# wifi.net
KiCad netlist of a schematic drawn in Altium Designer
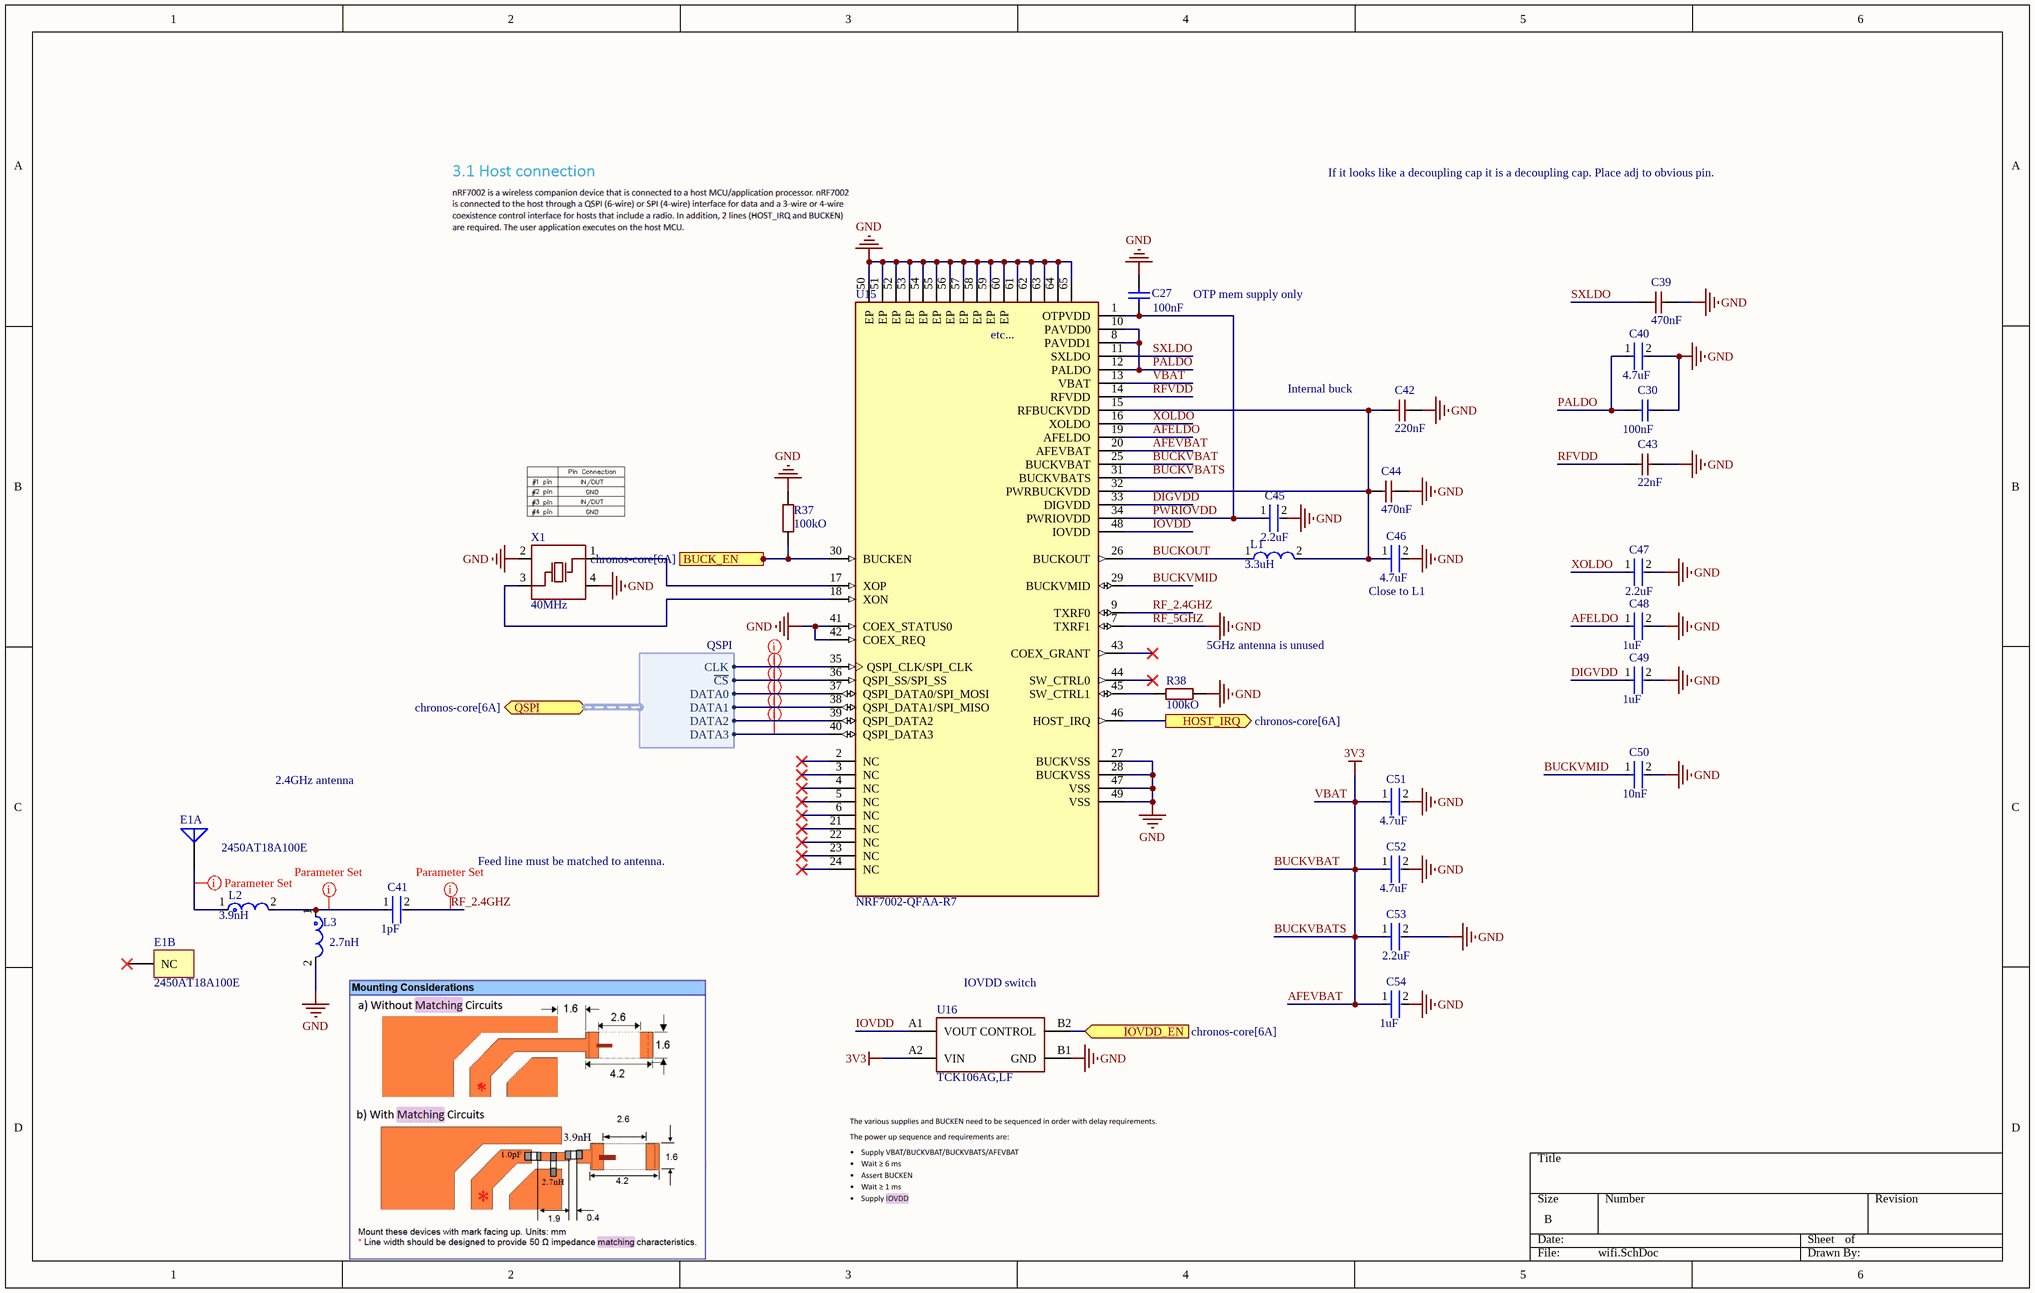
[diagram p0: wifi.SchDoc]

(export (version "E")
  (design (tool "Eeschema 10.0.6"))
  (components
    (comp (ref "C27")
      (value "CL05B104KO5NNNC")
      (footprint "CAPC1050X55X23ML05T13")
      (description "Chip Capacitor, 100 nF, +/- 10%, 16 V, -55 to 125 degC, 0402 (1005 Metric), RoHS, Tape and Reel")
      (fields (field (name "MANUFACTURER") "Samsung Electro-Mechanics") (field (name "CAPACITANCE") "100nF"))
      (libsource (lib "Altium Content Vault") (part "CAP-NP-2"))
    )
    (comp (ref "C30")
      (value "CL05B104KO5NNNC")
      (footprint "CAPC1050X55X23ML05T13")
      (description "Chip Capacitor, 100 nF, +/- 10%, 16 V, -55 to 125 degC, 0402 (1005 Metric), RoHS, Tape and Reel")
      (fields (field (name "MANUFACTURER") "Samsung Electro-Mechanics") (field (name "CAPACITANCE") "100nF"))
      (libsource (lib "Altium Content Vault") (part "CAP-NP-2"))
    )
    (comp (ref "C39")
      (value "470nF")
      (footprint "CL10B474KA8NNNC")
      (fields
        (field (name "JLCPCB PART #") "C1623")
        (field (name "MANUFACTURER PART NUMBER") "CL10B474KA8NNNC")
        (field (name "MANUFACTURER") "Samsung Electro-Mechanics")
      )
      (libsource (lib "CL10B474KA8NNNC") (part "CL10B474KA8NNNC"))
    )
    (comp (ref "C40")
      (value "CL05A475MP5NRNC")
      (footprint "FP-CL282-IPC_C")
      (description "Cap Ceramic 4.7uF 10V X5R ±20% SMD 0402 +85°C Paper T/R")
      (fields (field (name "CAPACITANCE") "4.7uF") (field (name "TOLERANCE") "20%"))
      (libsource (lib "Altium Content Vault") (part "b4654b650e69147ec39a6b967a45e02"))
    )
    (comp (ref "C41")
      (value "GJM1555C1H1R0BB01D")
      (footprint "FP-GJM155-0_05-IPC_B")
      (description "Multi-Layer Ceramic Capacitor 1pF C0G  ±0.1pF 0402 Paper T/R")
      (fields (field (name "CAPACITANCE") "1pF") (field (name "VOLTAGE") "50V"))
      (libsource (lib "Altium Content Vault") (part "02cd4be3c70576c341d710602a673aa"))
    )
    (comp (ref "C42")
      (value "220nF")
      (footprint "CL05B224KO5NNNC")
      (fields
        (field (name "JLCPCB PART #") "C16772")
        (field (name "MANUFACTURER PART NUMBER") "CL05B224KO5NNNC")
        (field (name "MANUFACTURER") "Samsung Electro-Mechanics")
      )
      (libsource (lib "CL05B224KO5NNNC") (part "CL05B224KO5NNNC"))
    )
    (comp (ref "C43")
      (value "22nF")
      (footprint "0402B223K500NT")
      (fields
        (field (name "JLCPCB PART #") "C1532")
        (field (name "MANUFACTURER PART NUMBER") "0402B223K500NT")
        (field (name "MANUFACTURER") "FH (Guangdong Fenghua Advanced Tech)")
      )
      (libsource (lib "0402B223K500NT") (part "0402B223K500NT"))
    )
    (comp (ref "C44")
      (value "470nF")
      (footprint "CL10B474KA8NNNC")
      (fields
        (field (name "JLCPCB PART #") "C1623")
        (field (name "MANUFACTURER PART NUMBER") "CL10B474KA8NNNC")
        (field (name "MANUFACTURER") "Samsung Electro-Mechanics")
      )
      (libsource (lib "CL10B474KA8NNNC") (part "CL10B474KA8NNNC"))
    )
    (comp (ref "C45")
      (value "CL05A225MQ5NSNC")
      (footprint "FP-CL50-IPC_C")
      (description "Cap Ceramic 2.2uF 6.3V X5R ±20% SMD 0402 +85°C Paper T/R")
      (fields (field (name "CAPACITANCE") "2.2uF") (field (name "TOLERANCE") "20%"))
      (libsource (lib "Altium Content Vault") (part "b4654b650e69147ec39a6b967a45e02"))
    )
    (comp (ref "C46")
      (value "CL05A475MP5NRNC")
      (footprint "FP-CL282-IPC_C")
      (description "Cap Ceramic 4.7uF 10V X5R ±20% SMD 0402 +85°C Paper T/R")
      (fields (field (name "CAPACITANCE") "4.7uF") (field (name "TOLERANCE") "20%"))
      (libsource (lib "Altium Content Vault") (part "b4654b650e69147ec39a6b967a45e02"))
    )
    (comp (ref "C47")
      (value "CL05A225MQ5NSNC")
      (footprint "FP-CL50-IPC_C")
      (description "Cap Ceramic 2.2uF 6.3V X5R ±20% SMD 0402 +85°C Paper T/R")
      (fields (field (name "CAPACITANCE") "2.2uF") (field (name "TOLERANCE") "20%"))
      (libsource (lib "Altium Content Vault") (part "b4654b650e69147ec39a6b967a45e02"))
    )
    (comp (ref "C48")
      (value "CL05A105KA5NQNC")
      (footprint "FP-CL542-IPC_C")
      (description "Cap Ceramic 1uF 25V X5R ±10% SMD 0402 +85°C Paper T/R")
      (fields (field (name "CAPACITANCE") "1uF") (field (name "TOLERANCE") "10%"))
      (libsource (lib "Altium Content Vault") (part "b4654b650e69147ec39a6b967a45e02"))
    )
    (comp (ref "C49")
      (value "CL05A105KA5NQNC")
      (footprint "FP-CL542-IPC_C")
      (description "Cap Ceramic 1uF 25V X5R ±10% SMD 0402 +85°C Paper T/R")
      (fields (field (name "CAPACITANCE") "1uF") (field (name "TOLERANCE") "10%"))
      (libsource (lib "Altium Content Vault") (part "b4654b650e69147ec39a6b967a45e02"))
    )
    (comp (ref "C50")
      (value "CL05B103KB5NNNC")
      (footprint "FP-CL165-IPC_C")
      (description "Cap Ceramic 10nF 50V X7R ±10% SMD 0402 +125°C Paper T/R")
      (fields
        (field (name "VOLTAGE") "50V")
        (field (name "TOLERANCE") "10%")
        (field (name "CAPACITANCE") "10nF")
      )
      (libsource (lib "Altium Content Vault") (part "b4654b650e69147ec39a6b967a45e02"))
    )
    (comp (ref "C51")
      (value "CL05A475MP5NRNC")
      (footprint "FP-CL282-IPC_C")
      (description "Cap Ceramic 4.7uF 10V X5R ±20% SMD 0402 +85°C Paper T/R")
      (fields (field (name "CAPACITANCE") "4.7uF") (field (name "TOLERANCE") "20%"))
      (libsource (lib "Altium Content Vault") (part "b4654b650e69147ec39a6b967a45e02"))
    )
    (comp (ref "C52")
      (value "CL05A475MP5NRNC")
      (footprint "FP-CL282-IPC_C")
      (description "Cap Ceramic 4.7uF 10V X5R ±20% SMD 0402 +85°C Paper T/R")
      (fields (field (name "CAPACITANCE") "4.7uF") (field (name "TOLERANCE") "20%"))
      (libsource (lib "Altium Content Vault") (part "b4654b650e69147ec39a6b967a45e02"))
    )
    (comp (ref "C53")
      (value "CL05A225MQ5NSNC")
      (footprint "FP-CL50-IPC_C")
      (description "Cap Ceramic 2.2uF 6.3V X5R ±20% SMD 0402 +85°C Paper T/R")
      (fields (field (name "CAPACITANCE") "2.2uF") (field (name "TOLERANCE") "20%"))
      (libsource (lib "Altium Content Vault") (part "b4654b650e69147ec39a6b967a45e02"))
    )
    (comp (ref "C54")
      (value "CL05A105KA5NQNC")
      (footprint "FP-CL542-IPC_C")
      (description "Cap Ceramic 1uF 25V X5R ±10% SMD 0402 +85°C Paper T/R")
      (fields (field (name "CAPACITANCE") "1uF") (field (name "TOLERANCE") "10%"))
      (libsource (lib "Altium Content Vault") (part "b4654b650e69147ec39a6b967a45e02"))
    )
    (comp (ref "E1")
      (value "2450AT18A100E")
      (footprint "JT-2450AT18A100-2_V")
      (description "Ceramic Antenna, 2.45 GHZ, 2 W, -40 to 125 degC, 2-Pin SMD, RoHS, Tape and Reel")
      (fields (field (name "MANUFACTURER") "Johanson Technology"))
      (libsource (lib "Altium Content Vault") (part "JT-2450AT18A100-2"))
    )
    (comp (ref "L1")
      (value "LQM2HPN3R3MGCL")
      (footprint "FP-LQM2HPN_G0-IPC_B")
      (description "Multilayer Type Inductor for Power Lines, 1008 (2520), 3.3μH, 20%, 0.2Ω, 1000mA")
      (fields (field (name "TOLERANCE") "20%") (field (name "INDUCTANCE") "3.3uH"))
      (libsource (lib "Altium Content Vault") (part "725321dda6339637d4d059423bc1c3c"))
    )
    (comp (ref "L2")
      (value "LQG15HS3N9S02D")
      (footprint "FP-LQG15HH_02-IPC_A")
      (description "Multilayer type RF Inductor 3.9nH ±0.3nH 0.14Ω 750mA 0402")
      (fields (field (name "INDUCTANCE") "3.9nH"))
      (libsource (lib "Altium Content Vault") (part "4cc4b267dca4c8e51f7102f422741d8"))
    )
    (comp (ref "L3")
      (value "LQG15HS2N7S02D")
      (footprint "FP-LQG15HH_02-IPC_C")
      (description "Multilayer type RF Inductor 2.7nH ±0.3nH 0.12Ω 800mA 0402")
      (fields (field (name "INDUCTANCE") "2.7nH"))
      (libsource (lib "Altium Content Vault") (part "4cc4b267dca4c8e51f7102f422741d8"))
    )
    (comp (ref "R37")
      (value "100kO")
      (footprint "0402WGF1003TCE")
      (fields
        (field (name "JLCPCB PART #") "C25741")
        (field (name "MANUFACTURER PART NUMBER") "0402WGF1003TCE")
        (field (name "MANUFACTURER") "UNI-ROYAL(Uniroyal Elec)")
      )
      (libsource (lib "") (part "0402WGF1003TCE_1"))
    )
    (comp (ref "R38")
      (value "100kO")
      (footprint "0402WGF1003TCE")
      (fields
        (field (name "JLCPCB PART #") "C25741")
        (field (name "MANUFACTURER PART NUMBER") "0402WGF1003TCE")
        (field (name "MANUFACTURER") "UNI-ROYAL(Uniroyal Elec)")
      )
      (libsource (lib "0402WGF1003TCE") (part "0402WGF1003TCE"))
    )
    (comp (ref "U15")
      (value "NRF7002-QFAA-R7")
      (footprint "IC_NRF7002-QFAA-R7")
      (description "IC RF TxRx Only WiFi 802.11a/b/g/-c/ax, Bluetooth, GPS 2.4GHz, 5GHz 48-VFQFN Exposed Pad")
      (fields (field (name "MF") "Nordic Semiconductors"))
      (libsource (lib "NRF7002-QFAA-R7") (part "NRF7002-QFAA-R7"))
    )
    (comp (ref "U16")
      (value "TCK106AG,LF")
      (footprint "TCK106AG,LF")
      (fields (field (name "JLCPCB PART #") "C2149807") (field (name "MANUFACTURER") "TOSHIBA"))
      (libsource (lib "TCK106AG,LF") (part "TCK106AG,LF"))
    )
    (comp (ref "X1")
      (value "40MHz")
      (footprint "TZ0308D")
      (description "Crystals. -30C~+85C 30ohm 40MHz 9pF Crystal Oscillator +/-10ppm SMD3225-4P Crystals ROHS")
      (fields (field (name "JLCPCB PART #") "C379787") (field (name "MANUFACTURER PART NUMBER") "TZ0308D"))
      (libsource (lib "TZ0308D") (part "TZ0308D"))
    )
  )
  (nets
    (net (code "2") (name "/AFELDO") (class "Default")
      (node (ref "C48") (pin "1") (pinfunction "1_1") (pintype "passive"))
      (node (ref "U15") (pin "19") (pinfunction "AFELDO_19") (pintype "power_in"))
    )
    (net (code "3") (name "/BUCKOUT") (class "Default")
      (node (ref "L1") (pin "1") (pinfunction "1_1") (pintype "passive"))
      (node (ref "U15") (pin "26") (pinfunction "BUCKOUT_26") (pintype "output"))
    )
    (net (code "4") (name "/BUCKVMID") (class "Default")
      (node (ref "C50") (pin "1") (pinfunction "1_1") (pintype "passive"))
      (node (ref "U15") (pin "29") (pinfunction "BUCKVMID_29") (pintype "bidirectional"))
    )
    (net (code "5") (name "/BUCK_EN") (class "Default")
      (node (ref "R37") (pin "1") (pinfunction "1_1") (pintype "passive"))
      (node (ref "U15") (pin "30") (pinfunction "BUCKEN_30") (pintype "input"))
    )
    (net (code "6") (name "/CLK") (class "Default")
      (node (ref "U15") (pin "35") (pinfunction "QSPI_CLK/SPI_CLK_35") (pintype "input"))
    )
    (net (code "7") (name "/DATA0") (class "Default")
      (node (ref "U15") (pin "37") (pinfunction "QSPI_DATA0/SPI_MOSI_37") (pintype "bidirectional"))
    )
    (net (code "8") (name "/DATA1") (class "Default")
      (node (ref "U15") (pin "38") (pinfunction "QSPI_DATA1/SPI_MISO_38") (pintype "bidirectional"))
    )
    (net (code "9") (name "/DATA2") (class "Default")
      (node (ref "U15") (pin "39") (pinfunction "QSPI_DATA2_39") (pintype "bidirectional"))
    )
    (net (code "10") (name "/DATA3") (class "Default")
      (node (ref "U15") (pin "40") (pinfunction "QSPI_DATA3_40") (pintype "bidirectional"))
    )
    (net (code "11") (name "/DIGVDD") (class "Default")
      (node (ref "C49") (pin "1") (pinfunction "1_1") (pintype "passive"))
      (node (ref "U15") (pin "33") (pinfunction "DIGVDD_33") (pintype "power_in"))
    )
    (net (code "12") (name "/HOST_IRQ") (class "Default")
      (node (ref "U15") (pin "46") (pinfunction "HOST_IRQ_46") (pintype "output"))
    )
    (net (code "13") (name "/IOVDD") (class "Default")
      (node (ref "U15") (pin "48") (pinfunction "IOVDD_48") (pintype "power_in"))
      (node (ref "U16") (pin "A1") (pinfunction "VOUT_A1") (pintype "passive"))
    )
    (net (code "14") (name "/IOVDD_EN") (class "Default")
      (node (ref "U16") (pin "B2") (pinfunction "CONTROL_B2") (pintype "passive"))
    )
    (net (code "15") (name "/PALDO") (class "Default")
      (node (ref "C30") (pin "2") (pinfunction "2_2") (pintype "passive"))
      (node (ref "C40") (pin "1") (pinfunction "1_1") (pintype "passive"))
      (node (ref "U15") (pin "10") (pinfunction "PAVDD0_10") (pintype "power_in"))
      (node (ref "U15") (pin "12") (pinfunction "PALDO_12") (pintype "power_in"))
      (node (ref "U15") (pin "8") (pinfunction "PAVDD1_8") (pintype "power_in"))
    )
    (net (code "16") (name "/PWRIOVDD") (class "Default")
      (node (ref "C27") (pin "1") (pinfunction "1_1") (pintype "passive"))
      (node (ref "C45") (pin "1") (pinfunction "1_1") (pintype "passive"))
      (node (ref "U15") (pin "1") (pinfunction "OTPVDD_1") (pintype "power_in"))
      (node (ref "U15") (pin "34") (pinfunction "PWRIOVDD_34") (pintype "power_in"))
    )
    (net (code "17") (name "/RFVDD") (class "Default")
      (node (ref "C43") (pin "1") (pinfunction "1_1") (pintype "passive"))
      (node (ref "U15") (pin "14") (pinfunction "RFVDD_14") (pintype "power_in"))
    )
    (net (code "18") (name "/RF_2.4GHZ") (class "Default")
      (node (ref "C41") (pin "2") (pinfunction "2_2") (pintype "passive"))
      (node (ref "U15") (pin "9") (pinfunction "TXRF0_9") (pintype "bidirectional"))
    )
    (net (code "19") (name "/SXLDO") (class "Default")
      (node (ref "C39") (pin "1") (pinfunction "1_1") (pintype "passive"))
      (node (ref "U15") (pin "11") (pinfunction "SXLDO_11") (pintype "power_in"))
    )
    (net (code "20") (name "/XOLDO") (class "Default")
      (node (ref "C47") (pin "1") (pinfunction "1_1") (pintype "passive"))
      (node (ref "U15") (pin "16") (pinfunction "XOLDO_16") (pintype "power_in"))
    )
    (net (code "22") (name "/~{CS}") (class "Default")
      (node (ref "U15") (pin "36") (pinfunction "QSPI_SS/SPI_SS_36") (pintype "input"))
    )
    (net (code "23") (name "3V3") (class "Default")
      (node (ref "C51") (pin "1") (pinfunction "1_1") (pintype "passive"))
      (node (ref "C52") (pin "1") (pinfunction "1_1") (pintype "passive"))
      (node (ref "C53") (pin "1") (pinfunction "1_1") (pintype "passive"))
      (node (ref "C54") (pin "1") (pinfunction "1_1") (pintype "passive"))
      (node (ref "U15") (pin "13") (pinfunction "VBAT_13") (pintype "power_in"))
      (node (ref "U15") (pin "20") (pinfunction "AFEVBAT_20") (pintype "power_in"))
      (node (ref "U15") (pin "25") (pinfunction "BUCKVBAT_25") (pintype "power_in"))
      (node (ref "U15") (pin "31") (pinfunction "BUCKVBATS_31") (pintype "power_in"))
      (node (ref "U16") (pin "A2") (pinfunction "VIN_A2") (pintype "passive"))
    )
    (net (code "24") (name "GND") (class "Default")
      (node (ref "C27") (pin "2") (pinfunction "2_2") (pintype "passive"))
      (node (ref "C30") (pin "1") (pinfunction "1_1") (pintype "passive"))
      (node (ref "C39") (pin "2") (pinfunction "2_2") (pintype "passive"))
      (node (ref "C40") (pin "2") (pinfunction "2_2") (pintype "passive"))
      (node (ref "C42") (pin "2") (pinfunction "2_2") (pintype "passive"))
      (node (ref "C43") (pin "2") (pinfunction "2_2") (pintype "passive"))
      (node (ref "C44") (pin "2") (pinfunction "2_2") (pintype "passive"))
      (node (ref "C45") (pin "2") (pinfunction "2_2") (pintype "passive"))
      (node (ref "C46") (pin "2") (pinfunction "2_2") (pintype "passive"))
      (node (ref "C47") (pin "2") (pinfunction "2_2") (pintype "passive"))
      (node (ref "C48") (pin "2") (pinfunction "2_2") (pintype "passive"))
      (node (ref "C49") (pin "2") (pinfunction "2_2") (pintype "passive"))
      (node (ref "C50") (pin "2") (pinfunction "2_2") (pintype "passive"))
      (node (ref "C51") (pin "2") (pinfunction "2_2") (pintype "passive"))
      (node (ref "C52") (pin "2") (pinfunction "2_2") (pintype "passive"))
      (node (ref "C53") (pin "2") (pinfunction "2_2") (pintype "passive"))
      (node (ref "C54") (pin "2") (pinfunction "2_2") (pintype "passive"))
      (node (ref "L3") (pin "2") (pinfunction "2_2") (pintype "passive"))
      (node (ref "R37") (pin "2") (pinfunction "2_2") (pintype "passive"))
      (node (ref "R38") (pin "2") (pinfunction "2_2") (pintype "passive"))
      (node (ref "U15") (pin "27") (pinfunction "BUCKVSS_27") (pintype "power_in"))
      (node (ref "U15") (pin "28") (pinfunction "BUCKVSS_28") (pintype "power_in"))
      (node (ref "U15") (pin "41") (pinfunction "COEX_STATUS0_41") (pintype "input"))
      (node (ref "U15") (pin "42") (pinfunction "COEX_REQ_42") (pintype "input"))
      (node (ref "U15") (pin "47") (pinfunction "VSS_47") (pintype "power_in"))
      (node (ref "U15") (pin "49") (pinfunction "VSS_49") (pintype "power_in"))
      (node (ref "U15") (pin "50") (pinfunction "EP_50") (pintype "passive"))
      (node (ref "U15") (pin "51") (pinfunction "EP_51") (pintype "passive"))
      (node (ref "U15") (pin "52") (pinfunction "EP_52") (pintype "passive"))
      (node (ref "U15") (pin "53") (pinfunction "EP_53") (pintype "passive"))
      (node (ref "U15") (pin "54") (pinfunction "EP_54") (pintype "passive"))
      (node (ref "U15") (pin "55") (pinfunction "EP_55") (pintype "passive"))
      (node (ref "U15") (pin "56") (pinfunction "EP_56") (pintype "passive"))
      (node (ref "U15") (pin "57") (pinfunction "EP_57") (pintype "passive"))
      (node (ref "U15") (pin "58") (pinfunction "EP_58") (pintype "passive"))
      (node (ref "U15") (pin "59") (pinfunction "EP_59") (pintype "passive"))
      (node (ref "U15") (pin "60") (pinfunction "EP_60") (pintype "passive"))
      (node (ref "U15") (pin "61") (pinfunction "EP_61") (pintype "passive"))
      (node (ref "U15") (pin "62") (pinfunction "EP_62") (pintype "passive"))
      (node (ref "U15") (pin "63") (pinfunction "EP_63") (pintype "passive"))
      (node (ref "U15") (pin "64") (pinfunction "EP_64") (pintype "passive"))
      (node (ref "U15") (pin "65") (pinfunction "EP_65") (pintype "passive"))
      (node (ref "U15") (pin "7") (pinfunction "TXRF1_7") (pintype "bidirectional"))
      (node (ref "U16") (pin "B1") (pinfunction "GND_B1") (pintype "passive"))
      (node (ref "X1") (pin "2") (pinfunction "GND_2") (pintype "passive"))
      (node (ref "X1") (pin "4") (pinfunction "GND_4") (pintype "passive"))
    )
    (net (code "25") (name "Net-(C41-Pad1)") (class "Default")
      (node (ref "C41") (pin "1") (pinfunction "1_1") (pintype "passive"))
      (node (ref "L2") (pin "2") (pinfunction "2_2") (pintype "passive"))
      (node (ref "L3") (pin "1") (pinfunction "1_1") (pintype "passive"))
    )
    (net (code "26") (name "Net-(E1A-FP)") (class "Default")
      (node (ref "E1") (pin "1") (pinfunction "FP_1") (pintype "passive"))
      (node (ref "L2") (pin "1") (pinfunction "1_1") (pintype "passive"))
    )
    (net (code "27") (name "Net-(U15-PWRBUCKVDD)") (class "Default")
      (node (ref "C42") (pin "1") (pinfunction "1_1") (pintype "passive"))
      (node (ref "C44") (pin "1") (pinfunction "1_1") (pintype "passive"))
      (node (ref "C46") (pin "1") (pinfunction "1_1") (pintype "passive"))
      (node (ref "L1") (pin "2") (pinfunction "2_2") (pintype "passive"))
      (node (ref "U15") (pin "15") (pinfunction "RFBUCKVDD_15") (pintype "power_in"))
      (node (ref "U15") (pin "32") (pinfunction "PWRBUCKVDD_32") (pintype "power_in"))
    )
    (net (code "28") (name "Net-(U15-SW_CTRL1)") (class "Default")
      (node (ref "R38") (pin "1") (pinfunction "1_1") (pintype "passive"))
      (node (ref "U15") (pin "45") (pinfunction "SW_CTRL1_45") (pintype "bidirectional"))
    )
    (net (code "29") (name "Net-(U15-XON)") (class "Default")
      (node (ref "U15") (pin "18") (pinfunction "XON_18") (pintype "input"))
      (node (ref "X1") (pin "3") (pinfunction "OSC2_3") (pintype "passive"))
    )
    (net (code "30") (name "Net-(U15-XOP)") (class "Default")
      (node (ref "U15") (pin "17") (pinfunction "XOP_17") (pintype "input"))
      (node (ref "X1") (pin "1") (pinfunction "OSC1_1") (pintype "passive"))
    )
    (net (code "31") (name "unconnected-(E1B-NC-Pad2)") (class "Default")
      (node (ref "E1") (pin "2") (pinfunction "NC_2") (pintype "passive+no_connect"))
    )
    (net (code "32") (name "unconnected-(U15-COEX_GRANT-Pad43)") (class "Default")
      (node (ref "U15") (pin "43") (pinfunction "COEX_GRANT_43") (pintype "output+no_connect"))
    )
    (net (code "33") (name "unconnected-(U15-NC-Pad2)") (class "Default")
      (node (ref "U15") (pin "2") (pinfunction "NC_2") (pintype "passive+no_connect"))
    )
    (net (code "34") (name "unconnected-(U15-NC-Pad3)") (class "Default")
      (node (ref "U15") (pin "3") (pinfunction "NC_3") (pintype "passive+no_connect"))
    )
    (net (code "35") (name "unconnected-(U15-NC-Pad4)") (class "Default")
      (node (ref "U15") (pin "4") (pinfunction "NC_4") (pintype "passive+no_connect"))
    )
    (net (code "36") (name "unconnected-(U15-NC-Pad5)") (class "Default")
      (node (ref "U15") (pin "5") (pinfunction "NC_5") (pintype "passive+no_connect"))
    )
    (net (code "37") (name "unconnected-(U15-NC-Pad6)") (class "Default")
      (node (ref "U15") (pin "6") (pinfunction "NC_6") (pintype "passive+no_connect"))
    )
    (net (code "38") (name "unconnected-(U15-NC-Pad21)") (class "Default")
      (node (ref "U15") (pin "21") (pinfunction "NC_21") (pintype "passive+no_connect"))
    )
    (net (code "39") (name "unconnected-(U15-NC-Pad22)") (class "Default")
      (node (ref "U15") (pin "22") (pinfunction "NC_22") (pintype "passive+no_connect"))
    )
    (net (code "40") (name "unconnected-(U15-NC-Pad23)") (class "Default")
      (node (ref "U15") (pin "23") (pinfunction "NC_23") (pintype "passive+no_connect"))
    )
    (net (code "41") (name "unconnected-(U15-NC-Pad24)") (class "Default")
      (node (ref "U15") (pin "24") (pinfunction "NC_24") (pintype "passive+no_connect"))
    )
    (net (code "42") (name "unconnected-(U15-SW_CTRL0-Pad44)") (class "Default")
      (node (ref "U15") (pin "44") (pinfunction "SW_CTRL0_44") (pintype "output+no_connect"))
    )
  )
)
